# arduino_mega_rs485.net
KiCad netlist of a schematic drawn in EAGLE
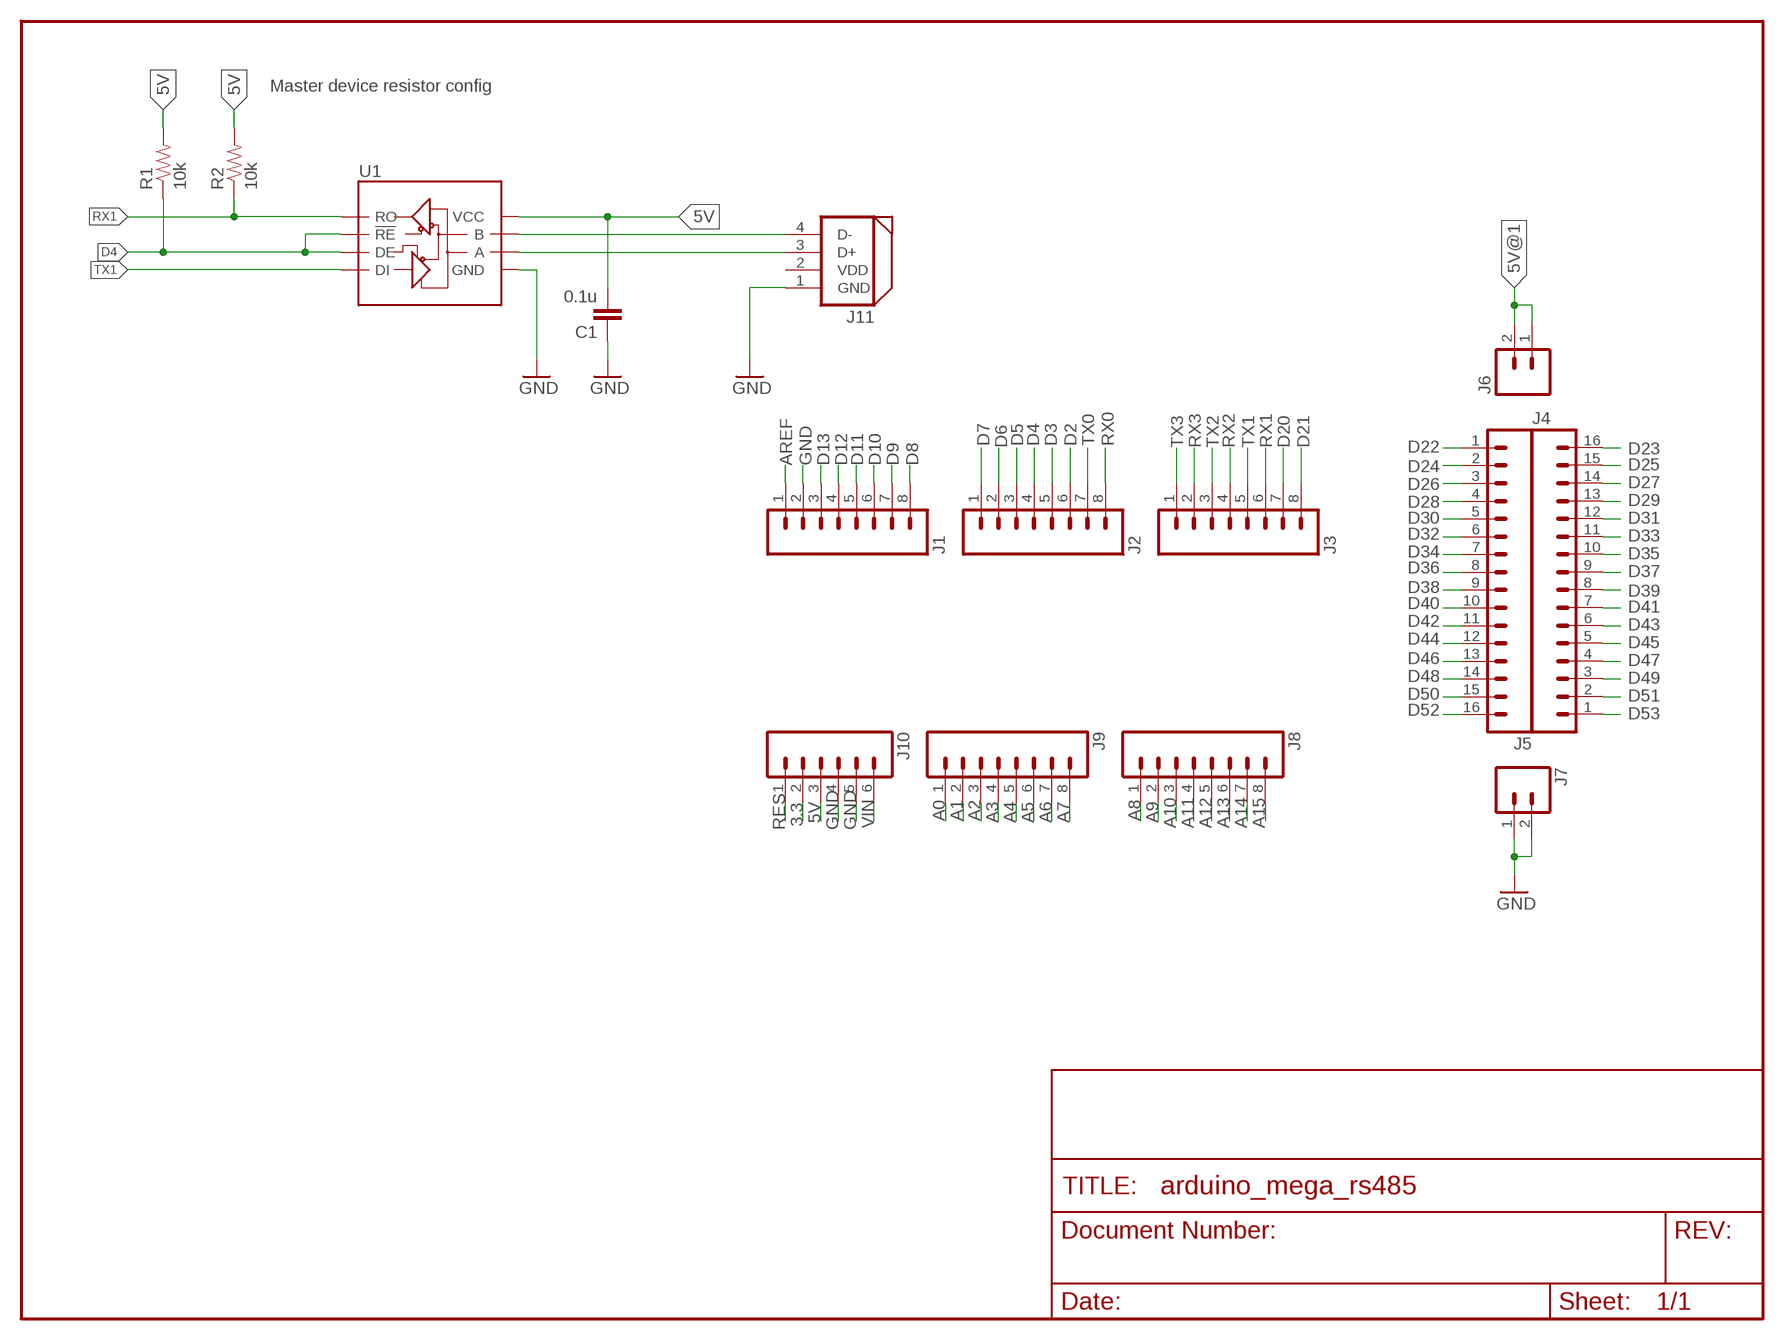
[diagram p0: schematic, sheet 1]

(export (version "E")
  (design (tool "Eeschema 10.0.6"))
  (components
    (comp (ref "C1")
      (value "0.1u")
      (footprint "eagle-import:CAP-PTH-SMALL")
      (libsource (lib "eagle-import") (part "CAPPTH"))
    )
    (comp (ref "J1")
      (value "M08LONGPADS")
      (footprint "eagle-import:1X08_LONGPADS")
      (libsource (lib "eagle-import") (part "M08LONGPADS"))
    )
    (comp (ref "J2")
      (value "M08LONGPADS")
      (footprint "eagle-import:1X08_LONGPADS")
      (libsource (lib "eagle-import") (part "M08LONGPADS"))
    )
    (comp (ref "J3")
      (value "M08LONGPADS")
      (footprint "eagle-import:1X08_LONGPADS")
      (libsource (lib "eagle-import") (part "M08LONGPADS"))
    )
    (comp (ref "J4")
      (value "M16PTH")
      (footprint "eagle-import:1X16")
      (libsource (lib "eagle-import") (part "M16PTH"))
    )
    (comp (ref "J5")
      (value "M16PTH")
      (footprint "eagle-import:1X16")
      (libsource (lib "eagle-import") (part "M16PTH"))
    )
    (comp (ref "J6")
      (value "M02PTH")
      (footprint "eagle-import:1X02")
      (libsource (lib "eagle-import") (part "M02PTH"))
    )
    (comp (ref "J7")
      (value "M02PTH")
      (footprint "eagle-import:1X02")
      (libsource (lib "eagle-import") (part "M02PTH"))
    )
    (comp (ref "J8")
      (value "M08LONGPADS")
      (footprint "eagle-import:1X08_LONGPADS")
      (libsource (lib "eagle-import") (part "M08LONGPADS"))
    )
    (comp (ref "J9")
      (value "M08LONGPADS")
      (footprint "eagle-import:1X08_LONGPADS")
      (libsource (lib "eagle-import") (part "M08LONGPADS"))
    )
    (comp (ref "J10")
      (value "M06LONGPADS")
      (footprint "eagle-import:1X06_LONGPADS")
      (libsource (lib "eagle-import") (part "M06LONGPADS"))
    )
    (comp (ref "J11")
      (value "DYNAMIXEL_RS485")
      (footprint "eagle-import:DYNAMIXEL_SPOX_04")
      (libsource (lib "eagle-import") (part "DYNAMIXEL_RS485"))
    )
    (comp (ref "R1")
      (value "10k")
      (footprint "eagle-import:AXIAL-0.4")
      (libsource (lib "eagle-import") (part "RESISTORPTH-1/4W"))
    )
    (comp (ref "R2")
      (value "10k")
      (footprint "eagle-import:AXIAL-0.4")
      (libsource (lib "eagle-import") (part "RESISTORPTH-1/4W"))
    )
    (comp (ref "U1")
      (value "RS485")
      (footprint "eagle-import:DIL08")
      (libsource (lib "eagle-import") (part "SN75176B"))
    )
  )
  (nets
    (net (code "1") (name "/3.3") (class "Default")
      (node (ref "J10") (pin "2") (pinfunction "2_2") (pintype "passive"))
    )
    (net (code "2") (name "/A0") (class "Default")
      (node (ref "J9") (pin "1") (pinfunction "1_1") (pintype "passive"))
    )
    (net (code "3") (name "/A1") (class "Default")
      (node (ref "J9") (pin "2") (pinfunction "2_2") (pintype "passive"))
    )
    (net (code "4") (name "/A2") (class "Default")
      (node (ref "J9") (pin "3") (pinfunction "3_3") (pintype "passive"))
    )
    (net (code "5") (name "/A3") (class "Default")
      (node (ref "J9") (pin "4") (pinfunction "4_4") (pintype "passive"))
    )
    (net (code "6") (name "/A4") (class "Default")
      (node (ref "J9") (pin "5") (pinfunction "5_5") (pintype "passive"))
    )
    (net (code "7") (name "/A5") (class "Default")
      (node (ref "J9") (pin "6") (pinfunction "6_6") (pintype "passive"))
    )
    (net (code "8") (name "/A6") (class "Default")
      (node (ref "J9") (pin "7") (pinfunction "7_7") (pintype "passive"))
    )
    (net (code "9") (name "/A7") (class "Default")
      (node (ref "J9") (pin "8") (pinfunction "8_8") (pintype "passive"))
    )
    (net (code "10") (name "/A8") (class "Default")
      (node (ref "J8") (pin "1") (pinfunction "1_1") (pintype "passive"))
    )
    (net (code "11") (name "/A9") (class "Default")
      (node (ref "J8") (pin "2") (pinfunction "2_2") (pintype "passive"))
    )
    (net (code "12") (name "/A10") (class "Default")
      (node (ref "J8") (pin "3") (pinfunction "3_3") (pintype "passive"))
    )
    (net (code "13") (name "/A11") (class "Default")
      (node (ref "J8") (pin "4") (pinfunction "4_4") (pintype "passive"))
    )
    (net (code "14") (name "/A12") (class "Default")
      (node (ref "J8") (pin "5") (pinfunction "5_5") (pintype "passive"))
    )
    (net (code "15") (name "/A13") (class "Default")
      (node (ref "J8") (pin "6") (pinfunction "6_6") (pintype "passive"))
    )
    (net (code "16") (name "/A14") (class "Default")
      (node (ref "J8") (pin "7") (pinfunction "7_7") (pintype "passive"))
    )
    (net (code "17") (name "/A15") (class "Default")
      (node (ref "J8") (pin "8") (pinfunction "8_8") (pintype "passive"))
    )
    (net (code "18") (name "/AREF") (class "Default")
      (node (ref "J1") (pin "1") (pinfunction "1_1") (pintype "passive"))
    )
    (net (code "19") (name "/D2") (class "Default")
      (node (ref "J2") (pin "6") (pinfunction "6_6") (pintype "passive"))
    )
    (net (code "20") (name "/D3") (class "Default")
      (node (ref "J2") (pin "5") (pinfunction "5_5") (pintype "passive"))
    )
    (net (code "21") (name "/D5") (class "Default")
      (node (ref "J2") (pin "3") (pinfunction "3_3") (pintype "passive"))
    )
    (net (code "22") (name "/D6") (class "Default")
      (node (ref "J2") (pin "2") (pinfunction "2_2") (pintype "passive"))
    )
    (net (code "23") (name "/D7") (class "Default")
      (node (ref "J2") (pin "1") (pinfunction "1_1") (pintype "passive"))
    )
    (net (code "24") (name "/D8") (class "Default")
      (node (ref "J1") (pin "8") (pinfunction "8_8") (pintype "passive"))
    )
    (net (code "25") (name "/D9") (class "Default")
      (node (ref "J1") (pin "7") (pinfunction "7_7") (pintype "passive"))
    )
    (net (code "26") (name "/D10") (class "Default")
      (node (ref "J1") (pin "6") (pinfunction "6_6") (pintype "passive"))
    )
    (net (code "27") (name "/D11") (class "Default")
      (node (ref "J1") (pin "5") (pinfunction "5_5") (pintype "passive"))
    )
    (net (code "28") (name "/D12") (class "Default")
      (node (ref "J1") (pin "4") (pinfunction "4_4") (pintype "passive"))
    )
    (net (code "29") (name "/D13") (class "Default")
      (node (ref "J1") (pin "3") (pinfunction "3_3") (pintype "passive"))
    )
    (net (code "30") (name "/D20") (class "Default")
      (node (ref "J3") (pin "7") (pinfunction "7_7") (pintype "passive"))
    )
    (net (code "31") (name "/D21") (class "Default")
      (node (ref "J3") (pin "8") (pinfunction "8_8") (pintype "passive"))
    )
    (net (code "32") (name "/D22") (class "Default")
      (node (ref "J5") (pin "1") (pinfunction "1_1") (pintype "passive"))
    )
    (net (code "33") (name "/D23") (class "Default")
      (node (ref "J4") (pin "16") (pinfunction "16_16") (pintype "passive"))
    )
    (net (code "34") (name "/D24") (class "Default")
      (node (ref "J5") (pin "2") (pinfunction "2_2") (pintype "passive"))
    )
    (net (code "35") (name "/D25") (class "Default")
      (node (ref "J4") (pin "15") (pinfunction "15_15") (pintype "passive"))
    )
    (net (code "36") (name "/D26") (class "Default")
      (node (ref "J5") (pin "3") (pinfunction "3_3") (pintype "passive"))
    )
    (net (code "37") (name "/D27") (class "Default")
      (node (ref "J4") (pin "14") (pinfunction "14_14") (pintype "passive"))
    )
    (net (code "38") (name "/D28") (class "Default")
      (node (ref "J5") (pin "4") (pinfunction "4_4") (pintype "passive"))
    )
    (net (code "39") (name "/D29") (class "Default")
      (node (ref "J4") (pin "13") (pinfunction "13_13") (pintype "passive"))
    )
    (net (code "40") (name "/D30") (class "Default")
      (node (ref "J5") (pin "5") (pinfunction "5_5") (pintype "passive"))
    )
    (net (code "41") (name "/D31") (class "Default")
      (node (ref "J4") (pin "12") (pinfunction "12_12") (pintype "passive"))
    )
    (net (code "42") (name "/D32") (class "Default")
      (node (ref "J5") (pin "6") (pinfunction "6_6") (pintype "passive"))
    )
    (net (code "43") (name "/D33") (class "Default")
      (node (ref "J4") (pin "11") (pinfunction "11_11") (pintype "passive"))
    )
    (net (code "44") (name "/D34") (class "Default")
      (node (ref "J5") (pin "7") (pinfunction "7_7") (pintype "passive"))
    )
    (net (code "45") (name "/D35") (class "Default")
      (node (ref "J4") (pin "10") (pinfunction "10_10") (pintype "passive"))
    )
    (net (code "46") (name "/D36") (class "Default")
      (node (ref "J5") (pin "8") (pinfunction "8_8") (pintype "passive"))
    )
    (net (code "47") (name "/D37") (class "Default")
      (node (ref "J4") (pin "9") (pinfunction "9_9") (pintype "passive"))
    )
    (net (code "48") (name "/D38") (class "Default")
      (node (ref "J5") (pin "9") (pinfunction "9_9") (pintype "passive"))
    )
    (net (code "49") (name "/D39") (class "Default")
      (node (ref "J4") (pin "8") (pinfunction "8_8") (pintype "passive"))
    )
    (net (code "50") (name "/D40") (class "Default")
      (node (ref "J5") (pin "10") (pinfunction "10_10") (pintype "passive"))
    )
    (net (code "51") (name "/D41") (class "Default")
      (node (ref "J4") (pin "7") (pinfunction "7_7") (pintype "passive"))
    )
    (net (code "52") (name "/D42") (class "Default")
      (node (ref "J5") (pin "11") (pinfunction "11_11") (pintype "passive"))
    )
    (net (code "53") (name "/D43") (class "Default")
      (node (ref "J4") (pin "6") (pinfunction "6_6") (pintype "passive"))
    )
    (net (code "54") (name "/D44") (class "Default")
      (node (ref "J5") (pin "12") (pinfunction "12_12") (pintype "passive"))
    )
    (net (code "55") (name "/D45") (class "Default")
      (node (ref "J4") (pin "5") (pinfunction "5_5") (pintype "passive"))
    )
    (net (code "56") (name "/D46") (class "Default")
      (node (ref "J5") (pin "13") (pinfunction "13_13") (pintype "passive"))
    )
    (net (code "57") (name "/D47") (class "Default")
      (node (ref "J4") (pin "4") (pinfunction "4_4") (pintype "passive"))
    )
    (net (code "58") (name "/D48") (class "Default")
      (node (ref "J5") (pin "14") (pinfunction "14_14") (pintype "passive"))
    )
    (net (code "59") (name "/D49") (class "Default")
      (node (ref "J4") (pin "3") (pinfunction "3_3") (pintype "passive"))
    )
    (net (code "60") (name "/D50") (class "Default")
      (node (ref "J5") (pin "15") (pinfunction "15_15") (pintype "passive"))
    )
    (net (code "61") (name "/D51") (class "Default")
      (node (ref "J4") (pin "2") (pinfunction "2_2") (pintype "passive"))
    )
    (net (code "62") (name "/D52") (class "Default")
      (node (ref "J5") (pin "16") (pinfunction "16_16") (pintype "passive"))
    )
    (net (code "63") (name "/D53") (class "Default")
      (node (ref "J4") (pin "1") (pinfunction "1_1") (pintype "passive"))
    )
    (net (code "64") (name "/RES") (class "Default")
      (node (ref "J10") (pin "1") (pinfunction "1_1") (pintype "passive"))
    )
    (net (code "65") (name "/RX0") (class "Default")
      (node (ref "J2") (pin "8") (pinfunction "8_8") (pintype "passive"))
    )
    (net (code "66") (name "/RX2") (class "Default")
      (node (ref "J3") (pin "4") (pinfunction "4_4") (pintype "passive"))
    )
    (net (code "67") (name "/RX3") (class "Default")
      (node (ref "J3") (pin "2") (pinfunction "2_2") (pintype "passive"))
    )
    (net (code "68") (name "/TX0") (class "Default")
      (node (ref "J2") (pin "7") (pinfunction "7_7") (pintype "passive"))
    )
    (net (code "69") (name "/TX2") (class "Default")
      (node (ref "J3") (pin "3") (pinfunction "3_3") (pintype "passive"))
    )
    (net (code "70") (name "/TX3") (class "Default")
      (node (ref "J3") (pin "1") (pinfunction "1_1") (pintype "passive"))
    )
    (net (code "71") (name "/VDD") (class "Default")
      (node (ref "J11") (pin "2") (pinfunction "VDD_2") (pintype "power_in"))
    )
    (net (code "72") (name "/VIN") (class "Default")
      (node (ref "J10") (pin "6") (pinfunction "6_6") (pintype "passive"))
    )
    (net (code "73") (name "5V") (class "Default")
      (node (ref "C1") (pin "2") (pinfunction "2_2") (pintype "passive"))
      (node (ref "J10") (pin "3") (pinfunction "3_3") (pintype "passive"))
      (node (ref "R1") (pin "P$2") (pinfunction "2_P$2") (pintype "passive"))
      (node (ref "R2") (pin "P$2") (pinfunction "2_P$2") (pintype "passive"))
      (node (ref "U1") (pin "8") (pinfunction "VCC_8") (pintype "bidirectional"))
    )
    (net (code "74") (name "5V@1") (class "Default")
      (node (ref "J6") (pin "1") (pinfunction "1_1") (pintype "passive"))
      (node (ref "J6") (pin "2") (pinfunction "2_2") (pintype "passive"))
    )
    (net (code "75") (name "D4") (class "Default")
      (node (ref "J2") (pin "4") (pinfunction "4_4") (pintype "passive"))
      (node (ref "R1") (pin "P$1") (pinfunction "1_P$1") (pintype "passive"))
      (node (ref "U1") (pin "2") (pinfunction "~{RE}_2") (pintype "bidirectional"))
      (node (ref "U1") (pin "3") (pinfunction "DE_3") (pintype "bidirectional"))
    )
    (net (code "76") (name "GND") (class "Default")
      (node (ref "C1") (pin "1") (pinfunction "1_1") (pintype "passive"))
      (node (ref "J1") (pin "2") (pinfunction "2_2") (pintype "passive"))
      (node (ref "J10") (pin "4") (pinfunction "4_4") (pintype "passive"))
      (node (ref "J10") (pin "5") (pinfunction "5_5") (pintype "passive"))
      (node (ref "J11") (pin "1") (pinfunction "GND_1") (pintype "power_in"))
      (node (ref "J7") (pin "1") (pinfunction "1_1") (pintype "passive"))
      (node (ref "J7") (pin "2") (pinfunction "2_2") (pintype "passive"))
      (node (ref "U1") (pin "5") (pinfunction "GND_5") (pintype "bidirectional"))
    )
    (net (code "77") (name "Net-(J11-D+)") (class "Default")
      (node (ref "J11") (pin "3") (pinfunction "D+_3") (pintype "bidirectional"))
      (node (ref "U1") (pin "6") (pinfunction "A_6") (pintype "bidirectional"))
    )
    (net (code "78") (name "Net-(J11-D-)") (class "Default")
      (node (ref "J11") (pin "4") (pinfunction "D-_4") (pintype "bidirectional"))
      (node (ref "U1") (pin "7") (pinfunction "B_7") (pintype "bidirectional"))
    )
    (net (code "79") (name "RX1") (class "Default")
      (node (ref "J3") (pin "6") (pinfunction "6_6") (pintype "passive"))
      (node (ref "R2") (pin "P$1") (pinfunction "1_P$1") (pintype "passive"))
      (node (ref "U1") (pin "1") (pinfunction "RO_1") (pintype "bidirectional"))
    )
    (net (code "80") (name "TX1") (class "Default")
      (node (ref "J3") (pin "5") (pinfunction "5_5") (pintype "passive"))
      (node (ref "U1") (pin "4") (pinfunction "DI_4") (pintype "bidirectional"))
    )
  )
)
